# PCB-Diagram_EasyEDA.net
KiCad netlist of a schematic drawn in EasyEDA
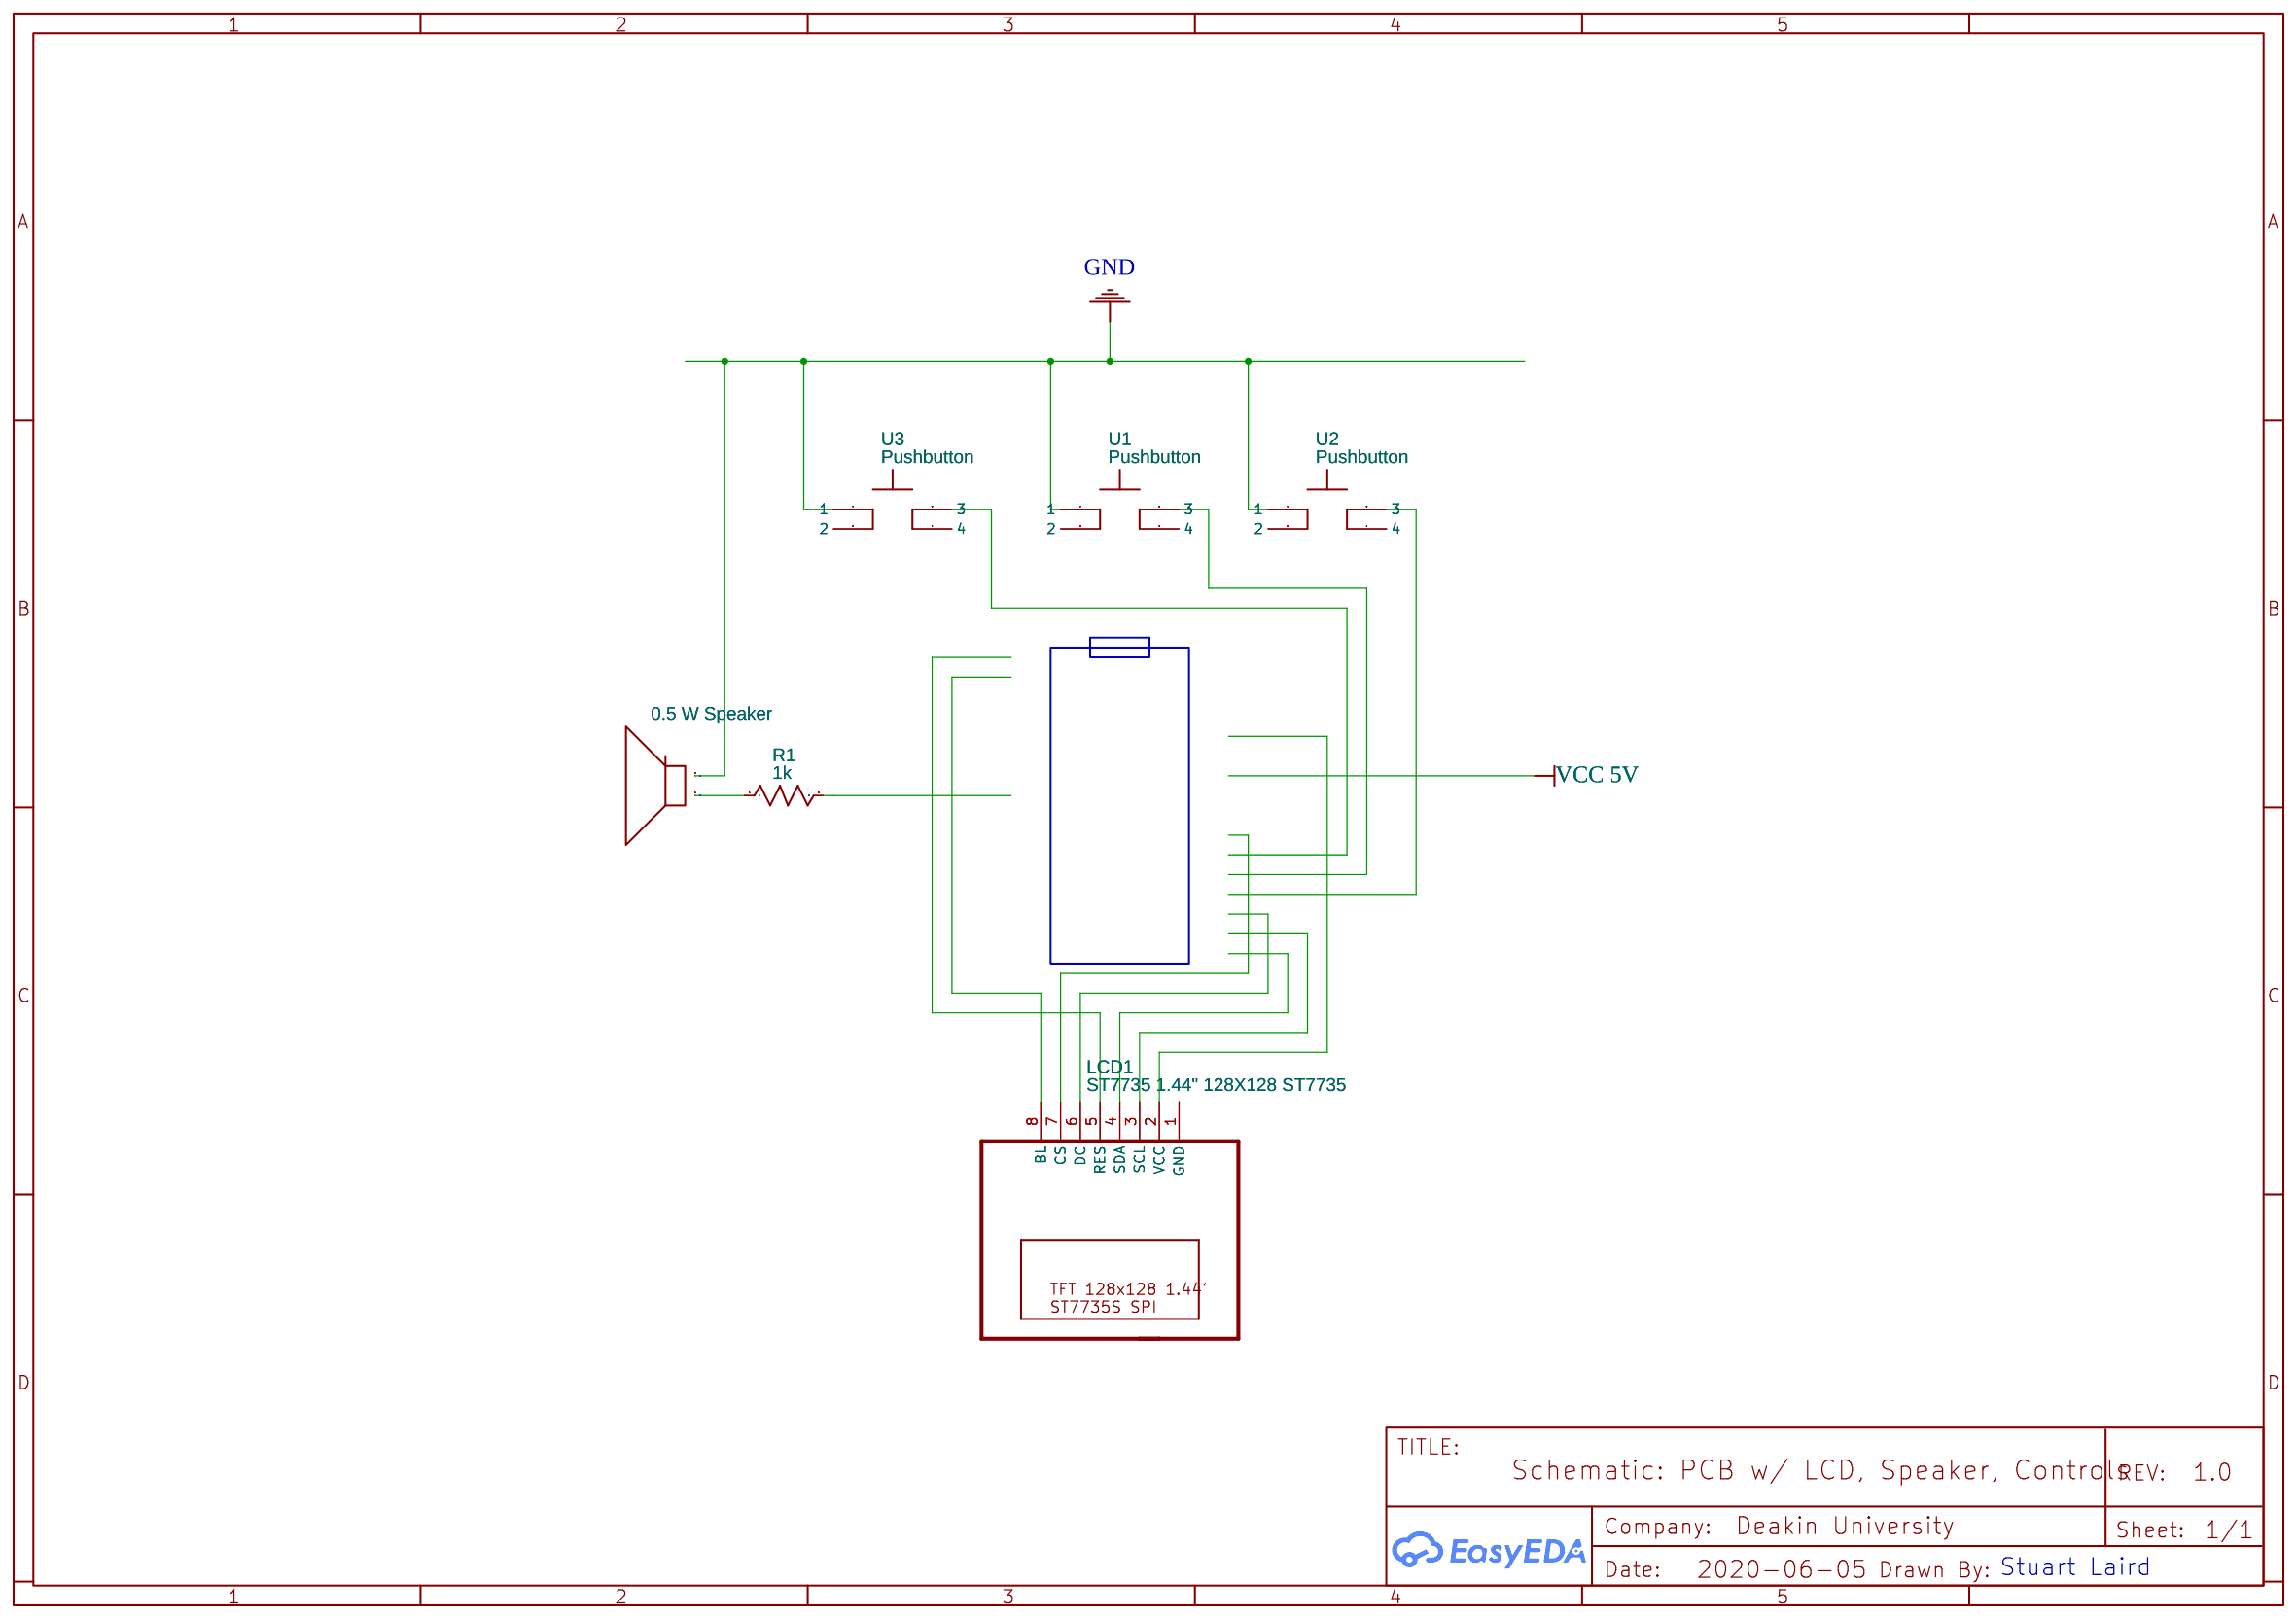
[diagram p0: schematic sheet]

(export (version "E")
  (design (tool "Eeschema 10.0.6"))
  (components
    (comp (ref "0.5WSPEAKER") (value "0.5 W Speaker") (libsource (lib "") (part "Speaker")))
    (comp (ref "LCD1")
      (value "ST7735 1.44\" 128X128 ST7735")
      (libsource (lib "") (part "ST7735 1.44{dblquote} 128X128 ST7735"))
    )
    (comp (ref "R1") (value "1k") (libsource (lib "") (part "R_0201_US")))
    (comp (ref "U1") (value "Pushbutton") (libsource (lib "") (part "Pushbutton")))
    (comp (ref "U2") (value "Pushbutton") (libsource (lib "") (part "Pushbutton")))
    (comp (ref "U3") (value "Pushbutton") (libsource (lib "") (part "Pushbutton")))
  )
  (nets
    (net (code "1") (name "GND") (class "Default")
      (node (ref "0.5WSPEAKER") (pin "2") (pinfunction "2_2") (pintype "unspecified"))
    )
    (net (code "2") (name "Net-(0.5WSPEAKER-Pad1)") (class "Default")
      (node (ref "0.5WSPEAKER") (pin "1") (pinfunction "1_1") (pintype "unspecified"))
      (node (ref "R1") (pin "1") (pinfunction "1_1") (pintype "unspecified"))
    )
    (net (code "4") (name "unconnected-(LCD1-BL-Pad8)") (class "Default")
      (node (ref "LCD1") (pin "8") (pinfunction "BL_8") (pintype "input"))
    )
    (net (code "5") (name "unconnected-(LCD1-CS-Pad7)") (class "Default")
      (node (ref "LCD1") (pin "7") (pinfunction "CS_7") (pintype "unspecified"))
    )
    (net (code "6") (name "unconnected-(LCD1-DC-Pad6)") (class "Default")
      (node (ref "LCD1") (pin "6") (pinfunction "DC_6") (pintype "input"))
    )
    (net (code "7") (name "unconnected-(LCD1-GND-Pad1)") (class "Default")
      (node (ref "LCD1") (pin "1") (pinfunction "GND_1") (pintype "passive"))
    )
    (net (code "8") (name "unconnected-(LCD1-RES-Pad5)") (class "Default")
      (node (ref "LCD1") (pin "5") (pinfunction "RES_5") (pintype "input"))
    )
    (net (code "9") (name "unconnected-(LCD1-SCL-Pad3)") (class "Default")
      (node (ref "LCD1") (pin "3") (pinfunction "SCL_3") (pintype "input"))
    )
    (net (code "10") (name "unconnected-(LCD1-SDA-Pad4)") (class "Default")
      (node (ref "LCD1") (pin "4") (pinfunction "SDA_4") (pintype "input"))
    )
    (net (code "11") (name "unconnected-(LCD1-VCC-Pad2)") (class "Default")
      (node (ref "LCD1") (pin "2") (pinfunction "VCC_2") (pintype "output"))
    )
    (net (code "12") (name "unconnected-(R1-Pad2)") (class "Default")
      (node (ref "R1") (pin "2") (pinfunction "2_2") (pintype "unspecified"))
    )
    (net (code "13") (name "unconnected-(U1-Pad1)") (class "Default")
      (node (ref "U1") (pin "1") (pinfunction "1_1") (pintype "unspecified"))
    )
    (net (code "14") (name "unconnected-(U1-Pad2)") (class "Default")
      (node (ref "U1") (pin "2") (pinfunction "2_2") (pintype "unspecified"))
    )
    (net (code "15") (name "unconnected-(U1-Pad3)") (class "Default")
      (node (ref "U1") (pin "3") (pinfunction "3_3") (pintype "unspecified"))
    )
    (net (code "16") (name "unconnected-(U1-Pad4)") (class "Default")
      (node (ref "U1") (pin "4") (pinfunction "4_4") (pintype "unspecified"))
    )
    (net (code "17") (name "unconnected-(U2-Pad1)") (class "Default")
      (node (ref "U2") (pin "1") (pinfunction "1_1") (pintype "unspecified"))
    )
    (net (code "18") (name "unconnected-(U2-Pad2)") (class "Default")
      (node (ref "U2") (pin "2") (pinfunction "2_2") (pintype "unspecified"))
    )
    (net (code "19") (name "unconnected-(U2-Pad3)") (class "Default")
      (node (ref "U2") (pin "3") (pinfunction "3_3") (pintype "unspecified"))
    )
    (net (code "20") (name "unconnected-(U2-Pad4)") (class "Default")
      (node (ref "U2") (pin "4") (pinfunction "4_4") (pintype "unspecified"))
    )
    (net (code "21") (name "unconnected-(U3-Pad1)") (class "Default")
      (node (ref "U3") (pin "1") (pinfunction "1_1") (pintype "unspecified"))
    )
    (net (code "22") (name "unconnected-(U3-Pad2)") (class "Default")
      (node (ref "U3") (pin "2") (pinfunction "2_2") (pintype "unspecified"))
    )
    (net (code "23") (name "unconnected-(U3-Pad3)") (class "Default")
      (node (ref "U3") (pin "3") (pinfunction "3_3") (pintype "unspecified"))
    )
    (net (code "24") (name "unconnected-(U3-Pad4)") (class "Default")
      (node (ref "U3") (pin "4") (pinfunction "4_4") (pintype "unspecified"))
    )
  )
)
